# USB_and_Power.net
KiCad netlist of a schematic drawn in Altium Designer
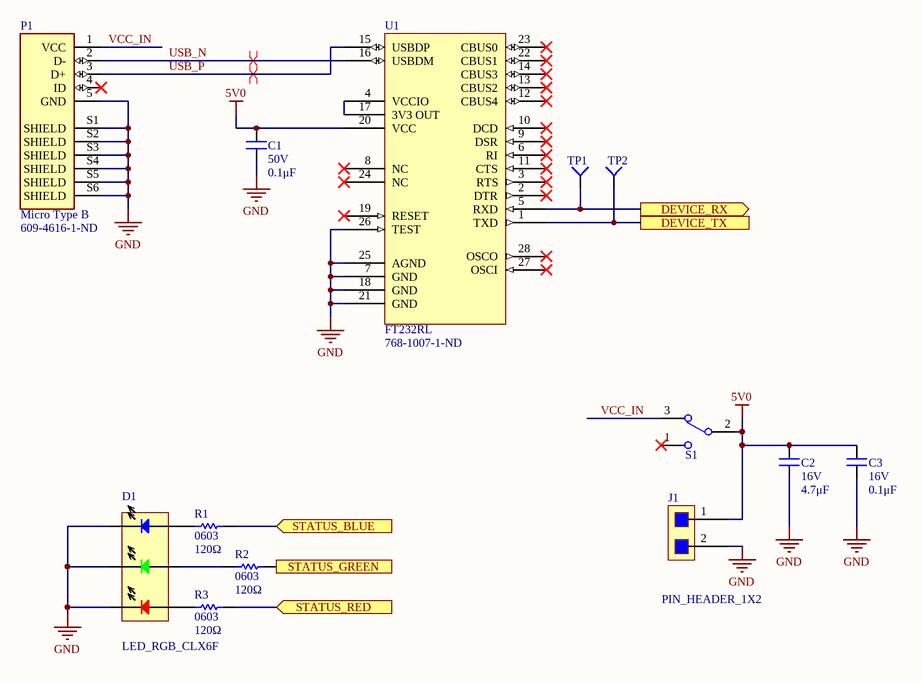
[diagram p0: USB and Power.SchDoc]

(export (version "E")
  (design (tool "Eeschema 10.0.6"))
  (components
    (comp (ref "C1")
      (value "0.1μF")
      (footprint "CAP0603")
      (description "CAP CER 0.1UF 50V X7R 0603")
      (fields (field (name "VOLTAGE RATING") "50V") (field (name "Comment") "CAP_0.1uF_50V_0603"))
      (libsource (lib "SKALE_LIB") (part "CAP_0.1uF_50V_0603"))
    )
    (comp (ref "C2")
      (value "4.7μF")
      (footprint "CAP0603")
      (description "CAP CER 4.7UF 16V X6S 0603")
      (fields (field (name "VOLTAGE RATING") "16V") (field (name "Comment") "CAP_4.7uF_16V_0603"))
      (libsource (lib "SKALE_LIB") (part "CAP_4.7uF_16V_0603"))
    )
    (comp (ref "C3")
      (value "0.1μF")
      (footprint "CAP0603")
      (description "CAP CER 0.1UF 16V X7R 0603")
      (fields (field (name "VOLTAGE RATING") "16V") (field (name "Comment") "CAP_0.1uF_16V_0603"))
      (libsource (lib "SKALE_LIB") (part "CAP_0.1uF_16V_0603"))
    )
    (comp (ref "D1")
      (value "LED_RGB_CLX6F")
      (footprint "SKALE_LIB:SOJ100P350X290-6N")
      (description "Visible LED")
      (fields
        (field (name "MP") "CLX6F-FKC-CKNNQDGBB7A363")
        (field (name "DIGI-KEY_PART_NUMBER") "CLX6F-FKC-CKNNQDGBB7A363CT-ND")
      )
      (libsource (lib "SKALE_LIB") (part "LED_RGB_CLX6F"))
    )
    (comp (ref "J1")
      (value "PIN_HEADER_1X2")
      (footprint "PIN_HEADER - 1X2")
      (description "Board Connector, 1 Contact(s), 1 Row(s), Male, Straight, Solder Terminal")
      (fields
        (field (name "MANUFACTURER") "Sullins")
        (field (name "MANUFACTURER PART NUMBER") "PREC001SAAN-RC")
      )
      (libsource (lib "SKALE_LIB") (part "PIN_HEADER_1X2"))
    )
    (comp (ref "P1")
      (value "Micro Type B")
      (footprint "FCI_10118193-0001LF")
      (description "USB Connector, 5 Contact(s), Female, Right Angle, Solder Terminal, Locking, Receptacle")
      (fields
        (field (name "MANUFACTURER") "Amphenol FCI")
        (field (name "MANUFACTURER PART NUMBER") "10118193-0001LF")
        (field (name "SUPPLIER PART NUMBER 1") "609-4616-1-ND")
      )
      (libsource (lib "HORNET_MOTOR_CONTROLLER") (part "USB Connector"))
    )
    (comp (ref "R1")
      (value "120Ω")
      (footprint "RES0603")
      (description "RES 120 OHM 5% 1/10W 0603")
      (fields (field (name "PACKAGE/FOOTPRINT") "0603") (field (name "Comment") "RES_120Ω_0603"))
      (libsource (lib "SKALE_LIB") (part "RES_120Ω_0603_5%"))
    )
    (comp (ref "R2")
      (value "120Ω")
      (footprint "RES0603")
      (description "RES 120 OHM 5% 1/10W 0603")
      (fields (field (name "PACKAGE/FOOTPRINT") "0603") (field (name "Comment") "RES_120Ω_0603"))
      (libsource (lib "SKALE_LIB") (part "RES_120Ω_0603_5%"))
    )
    (comp (ref "R3")
      (value "120Ω")
      (footprint "RES0603")
      (description "RES 120 OHM 5% 1/10W 0603")
      (fields (field (name "PACKAGE/FOOTPRINT") "0603") (field (name "Comment") "RES_120Ω_0603"))
      (libsource (lib "SKALE_LIB") (part "RES_120Ω_0603_5%"))
    )
    (comp (ref "S1")
      (value "SW_TOGGLE_SPDT")
      (footprint "100SP1T1B4M2QE")
      (description "SWITCH TOGGLE SPDT 5A 120V")
      (libsource (lib "SKALE_LIB") (part "SW_TOGGLE_SPDT"))
    )
    (comp (ref "TP1")
      (value "TESTPT")
      (footprint "TESTPT SQUARE")
      (libsource (lib "SKALE_LIB") (part "TESTPT SQUARE"))
    )
    (comp (ref "TP2")
      (value "TESTPT")
      (footprint "TESTPT SQUARE")
      (libsource (lib "SKALE_LIB") (part "TESTPT SQUARE"))
    )
    (comp (ref "U1")
      (value "FT232RL")
      (footprint "FT232RL")
      (description "USB Bus Controller, CMOS, PDSO28")
      (fields
        (field (name "MANUFACTURER") "FTDI")
        (field (name "MANUFACTURER PART NUMBER") "FT232RL-REEL")
        (field (name "SUPPLIER PART NUMBER 1") "768-1007-1-ND")
      )
      (libsource (lib "HORNET_MOTOR_CONTROLLER") (part "FT232RL"))
    )
  )
  (nets
    (net (code "1") (name "/DEVICE_RX") (class "Default")
      (node (ref "TP1") (pin "1") (pinfunction "=value_1") (pintype "passive"))
      (node (ref "U1") (pin "5") (pinfunction "RXD_5") (pintype "input"))
    )
    (net (code "2") (name "/DEVICE_TX") (class "Default")
      (node (ref "TP2") (pin "1") (pinfunction "=value_1") (pintype "passive"))
      (node (ref "U1") (pin "1") (pinfunction "TXD_1") (pintype "output"))
    )
    (net (code "3") (name "/STATUS_BLUE") (class "Default")
      (node (ref "R1") (pin "2") (pinfunction "2_2") (pintype "passive"))
    )
    (net (code "4") (name "/STATUS_GREEN") (class "Default")
      (node (ref "R2") (pin "2") (pinfunction "2_2") (pintype "passive"))
    )
    (net (code "5") (name "/STATUS_RED") (class "Default")
      (node (ref "R3") (pin "2") (pinfunction "2_2") (pintype "passive"))
    )
    (net (code "6") (name "/USB_N") (class "Default")
      (node (ref "P1") (pin "2") (pinfunction "D-_2") (pintype "bidirectional"))
      (node (ref "U1") (pin "16") (pinfunction "USBDM_16") (pintype "bidirectional"))
    )
    (net (code "7") (name "/USB_P") (class "Default")
      (node (ref "P1") (pin "3") (pinfunction "D+_3") (pintype "bidirectional"))
      (node (ref "U1") (pin "15") (pinfunction "USBDP_15") (pintype "bidirectional"))
    )
    (net (code "8") (name "/VCC_IN") (class "Default")
      (node (ref "P1") (pin "1") (pinfunction "VCC_1") (pintype "power_in"))
      (node (ref "S1") (pin "3") (pinfunction "3_3") (pintype "passive"))
    )
    (net (code "9") (name "5V0") (class "Default")
      (node (ref "C1") (pin "2") (pinfunction "2_2") (pintype "passive"))
      (node (ref "C2") (pin "2") (pinfunction "2_2") (pintype "passive"))
      (node (ref "C3") (pin "2") (pinfunction "2_2") (pintype "passive"))
      (node (ref "J1") (pin "1") (pinfunction "0_1") (pintype "passive"))
      (node (ref "S1") (pin "2") (pinfunction "2_2") (pintype "passive"))
      (node (ref "U1") (pin "20") (pinfunction "VCC_20") (pintype "power_in"))
    )
    (net (code "10") (name "GND") (class "Default")
      (node (ref "C1") (pin "1") (pinfunction "1_1") (pintype "passive"))
      (node (ref "C2") (pin "1") (pinfunction "1_1") (pintype "passive"))
      (node (ref "C3") (pin "1") (pinfunction "1_1") (pintype "passive"))
      (node (ref "D1") (pin "1") (pinfunction "BLUE_-_1") (pintype "passive"))
      (node (ref "D1") (pin "2") (pinfunction "GREEN_-_2") (pintype "passive"))
      (node (ref "D1") (pin "3") (pinfunction "RED_-_3") (pintype "passive"))
      (node (ref "J1") (pin "2") (pinfunction "0_2") (pintype "passive"))
      (node (ref "P1") (pin "5") (pinfunction "GND_5") (pintype "power_in"))
      (node (ref "P1") (pin "S1") (pinfunction "SHIELD_S1") (pintype "passive"))
      (node (ref "P1") (pin "S2") (pinfunction "SHIELD_S2") (pintype "passive"))
      (node (ref "P1") (pin "S3") (pinfunction "SHIELD_S3") (pintype "passive"))
      (node (ref "P1") (pin "S4") (pinfunction "SHIELD_S4") (pintype "passive"))
      (node (ref "P1") (pin "S5") (pinfunction "SHIELD_S5") (pintype "passive"))
      (node (ref "P1") (pin "S6") (pinfunction "SHIELD_S6") (pintype "passive"))
      (node (ref "U1") (pin "18") (pinfunction "GND_18") (pintype "power_in"))
      (node (ref "U1") (pin "21") (pinfunction "GND_21") (pintype "power_in"))
      (node (ref "U1") (pin "25") (pinfunction "AGND_25") (pintype "power_in"))
      (node (ref "U1") (pin "26") (pinfunction "TEST_26") (pintype "input"))
      (node (ref "U1") (pin "7") (pinfunction "GND_7") (pintype "power_in"))
    )
    (net (code "11") (name "Net-(D1-Blue_+)") (class "Default")
      (node (ref "D1") (pin "6") (pinfunction "Blue_+_6") (pintype "passive"))
      (node (ref "R1") (pin "1") (pinfunction "1_1") (pintype "passive"))
    )
    (net (code "12") (name "Net-(D1-Green_+)") (class "Default")
      (node (ref "D1") (pin "5") (pinfunction "Green_+_5") (pintype "passive"))
      (node (ref "R2") (pin "1") (pinfunction "1_1") (pintype "passive"))
    )
    (net (code "13") (name "Net-(D1-Red_+)") (class "Default")
      (node (ref "D1") (pin "4") (pinfunction "Red_+_4") (pintype "passive"))
      (node (ref "R3") (pin "1") (pinfunction "1_1") (pintype "passive"))
    )
    (net (code "14") (name "Net-(U1-3V3_OUT)") (class "Default")
      (node (ref "U1") (pin "17") (pinfunction "3V3_OUT_17") (pintype "power_in"))
      (node (ref "U1") (pin "4") (pinfunction "VCCIO_4") (pintype "power_in"))
    )
    (net (code "15") (name "unconnected-(P1-ID-Pad4)") (class "Default")
      (node (ref "P1") (pin "4") (pinfunction "ID_4") (pintype "bidirectional+no_connect"))
    )
    (net (code "16") (name "unconnected-(S1-Pad1)") (class "Default")
      (node (ref "S1") (pin "1") (pinfunction "1_1") (pintype "passive+no_connect"))
    )
    (net (code "17") (name "unconnected-(U1-CBUS0-Pad23)") (class "Default")
      (node (ref "U1") (pin "23") (pinfunction "CBUS0_23") (pintype "bidirectional+no_connect"))
    )
    (net (code "18") (name "unconnected-(U1-CBUS1-Pad22)") (class "Default")
      (node (ref "U1") (pin "22") (pinfunction "CBUS1_22") (pintype "bidirectional+no_connect"))
    )
    (net (code "19") (name "unconnected-(U1-CBUS2-Pad13)") (class "Default")
      (node (ref "U1") (pin "13") (pinfunction "CBUS2_13") (pintype "bidirectional+no_connect"))
    )
    (net (code "20") (name "unconnected-(U1-CBUS3-Pad14)") (class "Default")
      (node (ref "U1") (pin "14") (pinfunction "CBUS3_14") (pintype "bidirectional+no_connect"))
    )
    (net (code "21") (name "unconnected-(U1-CBUS4-Pad12)") (class "Default")
      (node (ref "U1") (pin "12") (pinfunction "CBUS4_12") (pintype "bidirectional+no_connect"))
    )
    (net (code "22") (name "unconnected-(U1-CTS-Pad11)") (class "Default")
      (node (ref "U1") (pin "11") (pinfunction "CTS_11") (pintype "input+no_connect"))
    )
    (net (code "23") (name "unconnected-(U1-DCD-Pad10)") (class "Default")
      (node (ref "U1") (pin "10") (pinfunction "DCD_10") (pintype "input+no_connect"))
    )
    (net (code "24") (name "unconnected-(U1-DSR-Pad9)") (class "Default")
      (node (ref "U1") (pin "9") (pinfunction "DSR_9") (pintype "input+no_connect"))
    )
    (net (code "25") (name "unconnected-(U1-DTR-Pad2)") (class "Default")
      (node (ref "U1") (pin "2") (pinfunction "DTR_2") (pintype "output+no_connect"))
    )
    (net (code "26") (name "unconnected-(U1-NC-Pad8)") (class "Default")
      (node (ref "U1") (pin "8") (pinfunction "NC_8") (pintype "passive+no_connect"))
    )
    (net (code "27") (name "unconnected-(U1-NC-Pad24)") (class "Default")
      (node (ref "U1") (pin "24") (pinfunction "NC_24") (pintype "passive+no_connect"))
    )
    (net (code "28") (name "unconnected-(U1-OSCI-Pad27)") (class "Default")
      (node (ref "U1") (pin "27") (pinfunction "OSCI_27") (pintype "input+no_connect"))
    )
    (net (code "29") (name "unconnected-(U1-OSCO-Pad28)") (class "Default")
      (node (ref "U1") (pin "28") (pinfunction "OSCO_28") (pintype "output+no_connect"))
    )
    (net (code "30") (name "unconnected-(U1-RESET-Pad19)") (class "Default")
      (node (ref "U1") (pin "19") (pinfunction "RESET_19") (pintype "input+no_connect"))
    )
    (net (code "31") (name "unconnected-(U1-RI-Pad6)") (class "Default")
      (node (ref "U1") (pin "6") (pinfunction "RI_6") (pintype "input+no_connect"))
    )
    (net (code "32") (name "unconnected-(U1-RTS-Pad3)") (class "Default")
      (node (ref "U1") (pin "3") (pinfunction "RTS_3") (pintype "output+no_connect"))
    )
  )
)
